# CON_RS485_PWR_RJ45.net
KiCad netlist of a schematic drawn in Altium Designer
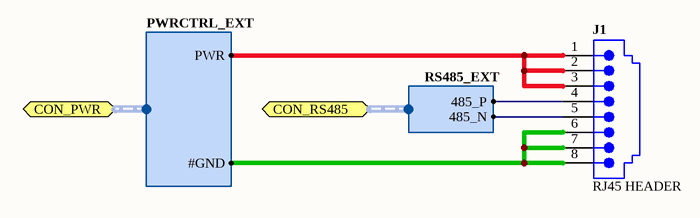
[diagram p0: CON_RS485_PWR_RJ45.SchDoc]

(export (version "E")
  (design (tool "Eeschema 10.0.6"))
  (components
    (comp (ref "J1")
      (value "RJ45 HEADER")
      (footprint "15-43-6233")
      (description "Connector, RJ45 Socket, Right-Angle, 8 Way (Ethernet), PCM8P8C")
      (libsource (lib "AltiumDesignLibrary") (part "CON-RJ45-8-RA"))
    )
  )
  (nets
    (net (code "3") (name "/#GND") (class "Default")
      (node (ref "J1") (pin "6") (pinfunction "6_6") (pintype "passive"))
      (node (ref "J1") (pin "7") (pinfunction "7_7") (pintype "passive"))
      (node (ref "J1") (pin "8") (pinfunction "8_8") (pintype "passive"))
    )
    (net (code "4") (name "/485_N") (class "Default")
      (node (ref "J1") (pin "5") (pinfunction "5_5") (pintype "passive"))
    )
    (net (code "5") (name "/485_P") (class "Default")
      (node (ref "J1") (pin "4") (pinfunction "4_4") (pintype "passive"))
    )
    (net (code "6") (name "/PWR") (class "Default")
      (node (ref "J1") (pin "1") (pinfunction "1_1") (pintype "passive"))
      (node (ref "J1") (pin "2") (pinfunction "2_2") (pintype "passive"))
      (node (ref "J1") (pin "3") (pinfunction "3_3") (pintype "passive"))
    )
  )
)
